# 6x6.net
KiCad netlist of a schematic drawn in EAGLE
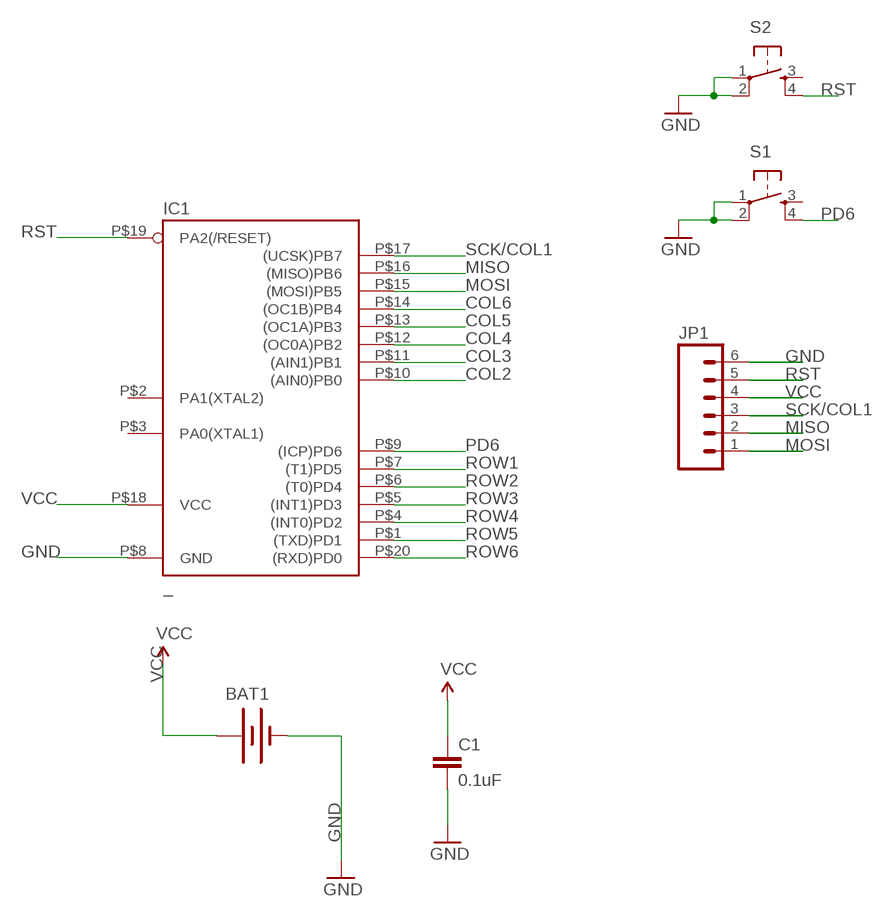
[diagram p0: schematic, sheet 1]
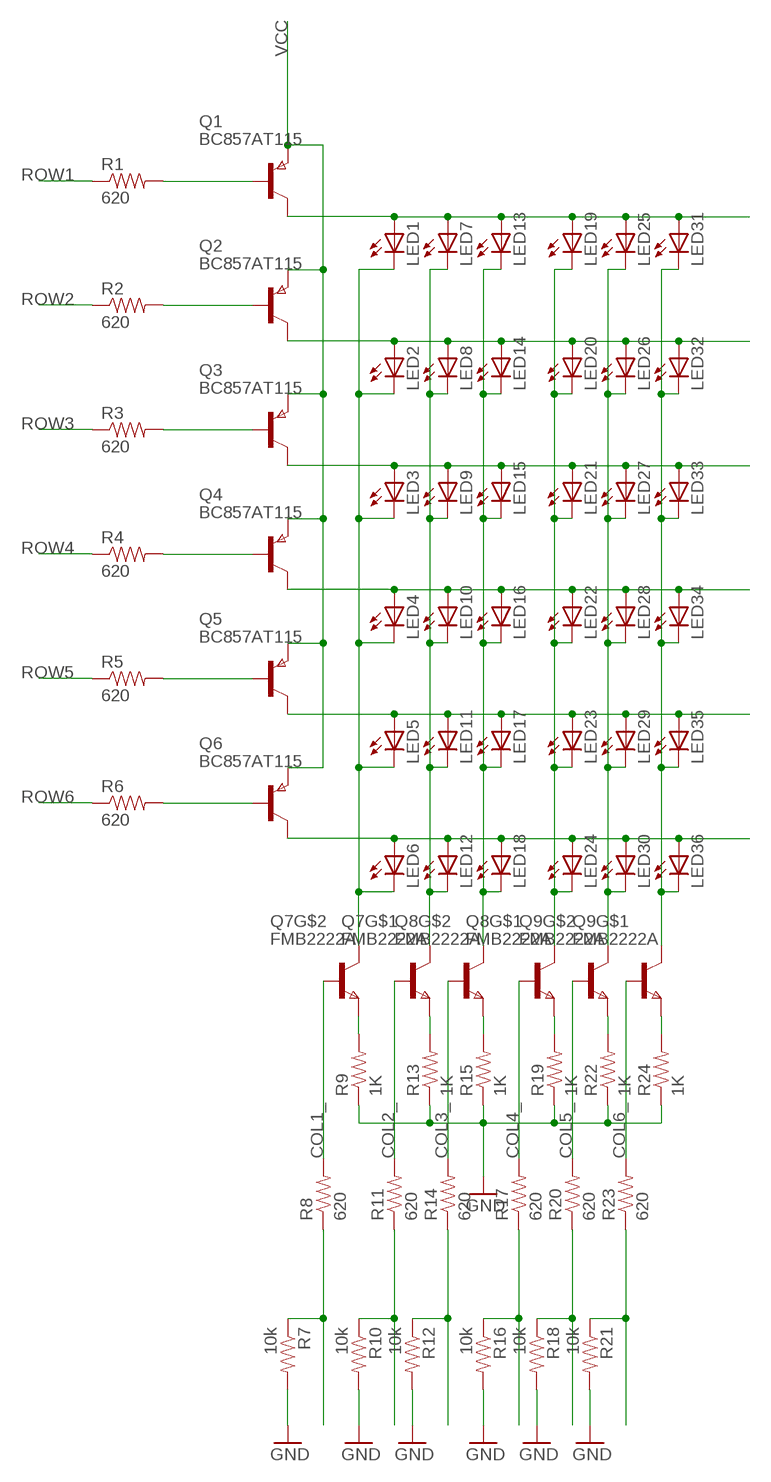
[diagram p1: schematic, sheet 2]

(export (version "E")
  (design (tool "Eeschema 10.0.6"))
  (components
    (comp (ref "BAT1")
      (value "BATTERY245MM")
      (footprint "eagle-import:BATTCON_245MM")
      (libsource (lib "eagle-import") (part "BATTERY245MM"))
    )
    (comp (ref "C1")
      (value "0.1uF")
      (footprint "eagle-import:0805")
      (libsource (lib "eagle-import") (part "CAP0805"))
    )
    (comp (ref "IC1")
      (value "_")
      (footprint "eagle-import:MLF20")
      (libsource (lib "eagle-import") (part "TINY2313-M"))
    )
    (comp (ref "JP1")
      (value "M061X06-SMD_EDGE_FEMALE")
      (footprint "eagle-import:1X06-SMD_EDGE")
      (libsource (lib "eagle-import") (part "M061X06-SMD_EDGE_FEMALE"))
    )
    (comp (ref "S1")
      (value "TAC_SWITCHSMD")
      (footprint "eagle-import:TACTILE_SWITCH_SMD")
      (libsource (lib "eagle-import") (part "TAC_SWITCHSMD"))
    )
    (comp (ref "S2")
      (value "TAC_SWITCHSMD")
      (footprint "eagle-import:TACTILE_SWITCH_SMD")
      (libsource (lib "eagle-import") (part "TAC_SWITCHSMD"))
    )
    (comp (ref "LED1")
      (value "LEDCHIPLED_1206")
      (footprint "eagle-import:CHIPLED_1206")
      (libsource (lib "eagle-import") (part "LEDCHIPLED_1206"))
    )
    (comp (ref "LED2")
      (value "LEDCHIPLED_1206")
      (footprint "eagle-import:CHIPLED_1206")
      (libsource (lib "eagle-import") (part "LEDCHIPLED_1206"))
    )
    (comp (ref "LED3")
      (value "LEDCHIPLED_1206")
      (footprint "eagle-import:CHIPLED_1206")
      (libsource (lib "eagle-import") (part "LEDCHIPLED_1206"))
    )
    (comp (ref "LED4")
      (value "LEDCHIPLED_1206")
      (footprint "eagle-import:CHIPLED_1206")
      (libsource (lib "eagle-import") (part "LEDCHIPLED_1206"))
    )
    (comp (ref "LED5")
      (value "LEDCHIPLED_1206")
      (footprint "eagle-import:CHIPLED_1206")
      (libsource (lib "eagle-import") (part "LEDCHIPLED_1206"))
    )
    (comp (ref "LED6")
      (value "LEDCHIPLED_1206")
      (footprint "eagle-import:CHIPLED_1206")
      (libsource (lib "eagle-import") (part "LEDCHIPLED_1206"))
    )
    (comp (ref "LED7")
      (value "LEDCHIPLED_1206")
      (footprint "eagle-import:CHIPLED_1206")
      (libsource (lib "eagle-import") (part "LEDCHIPLED_1206"))
    )
    (comp (ref "LED8")
      (value "LEDCHIPLED_1206")
      (footprint "eagle-import:CHIPLED_1206")
      (libsource (lib "eagle-import") (part "LEDCHIPLED_1206"))
    )
    (comp (ref "LED9")
      (value "LEDCHIPLED_1206")
      (footprint "eagle-import:CHIPLED_1206")
      (libsource (lib "eagle-import") (part "LEDCHIPLED_1206"))
    )
    (comp (ref "LED10")
      (value "LEDCHIPLED_1206")
      (footprint "eagle-import:CHIPLED_1206")
      (libsource (lib "eagle-import") (part "LEDCHIPLED_1206"))
    )
    (comp (ref "LED11")
      (value "LEDCHIPLED_1206")
      (footprint "eagle-import:CHIPLED_1206")
      (libsource (lib "eagle-import") (part "LEDCHIPLED_1206"))
    )
    (comp (ref "LED12")
      (value "LEDCHIPLED_1206")
      (footprint "eagle-import:CHIPLED_1206")
      (libsource (lib "eagle-import") (part "LEDCHIPLED_1206"))
    )
    (comp (ref "LED13")
      (value "LEDCHIPLED_1206")
      (footprint "eagle-import:CHIPLED_1206")
      (libsource (lib "eagle-import") (part "LEDCHIPLED_1206"))
    )
    (comp (ref "LED14")
      (value "LEDCHIPLED_1206")
      (footprint "eagle-import:CHIPLED_1206")
      (libsource (lib "eagle-import") (part "LEDCHIPLED_1206"))
    )
    (comp (ref "LED15")
      (value "LEDCHIPLED_1206")
      (footprint "eagle-import:CHIPLED_1206")
      (libsource (lib "eagle-import") (part "LEDCHIPLED_1206"))
    )
    (comp (ref "LED16")
      (value "LEDCHIPLED_1206")
      (footprint "eagle-import:CHIPLED_1206")
      (libsource (lib "eagle-import") (part "LEDCHIPLED_1206"))
    )
    (comp (ref "LED17")
      (value "LEDCHIPLED_1206")
      (footprint "eagle-import:CHIPLED_1206")
      (libsource (lib "eagle-import") (part "LEDCHIPLED_1206"))
    )
    (comp (ref "LED18")
      (value "LEDCHIPLED_1206")
      (footprint "eagle-import:CHIPLED_1206")
      (libsource (lib "eagle-import") (part "LEDCHIPLED_1206"))
    )
    (comp (ref "LED19")
      (value "LEDCHIPLED_1206")
      (footprint "eagle-import:CHIPLED_1206")
      (libsource (lib "eagle-import") (part "LEDCHIPLED_1206"))
    )
    (comp (ref "LED20")
      (value "LEDCHIPLED_1206")
      (footprint "eagle-import:CHIPLED_1206")
      (libsource (lib "eagle-import") (part "LEDCHIPLED_1206"))
    )
    (comp (ref "LED21")
      (value "LEDCHIPLED_1206")
      (footprint "eagle-import:CHIPLED_1206")
      (libsource (lib "eagle-import") (part "LEDCHIPLED_1206"))
    )
    (comp (ref "LED22")
      (value "LEDCHIPLED_1206")
      (footprint "eagle-import:CHIPLED_1206")
      (libsource (lib "eagle-import") (part "LEDCHIPLED_1206"))
    )
    (comp (ref "LED23")
      (value "LEDCHIPLED_1206")
      (footprint "eagle-import:CHIPLED_1206")
      (libsource (lib "eagle-import") (part "LEDCHIPLED_1206"))
    )
    (comp (ref "LED24")
      (value "LEDCHIPLED_1206")
      (footprint "eagle-import:CHIPLED_1206")
      (libsource (lib "eagle-import") (part "LEDCHIPLED_1206"))
    )
    (comp (ref "LED25")
      (value "LEDCHIPLED_1206")
      (footprint "eagle-import:CHIPLED_1206")
      (libsource (lib "eagle-import") (part "LEDCHIPLED_1206"))
    )
    (comp (ref "LED26")
      (value "LEDCHIPLED_1206")
      (footprint "eagle-import:CHIPLED_1206")
      (libsource (lib "eagle-import") (part "LEDCHIPLED_1206"))
    )
    (comp (ref "LED27")
      (value "LEDCHIPLED_1206")
      (footprint "eagle-import:CHIPLED_1206")
      (libsource (lib "eagle-import") (part "LEDCHIPLED_1206"))
    )
    (comp (ref "LED28")
      (value "LEDCHIPLED_1206")
      (footprint "eagle-import:CHIPLED_1206")
      (libsource (lib "eagle-import") (part "LEDCHIPLED_1206"))
    )
    (comp (ref "LED29")
      (value "LEDCHIPLED_1206")
      (footprint "eagle-import:CHIPLED_1206")
      (libsource (lib "eagle-import") (part "LEDCHIPLED_1206"))
    )
    (comp (ref "LED30")
      (value "LEDCHIPLED_1206")
      (footprint "eagle-import:CHIPLED_1206")
      (libsource (lib "eagle-import") (part "LEDCHIPLED_1206"))
    )
    (comp (ref "LED31")
      (value "LEDCHIPLED_1206")
      (footprint "eagle-import:CHIPLED_1206")
      (libsource (lib "eagle-import") (part "LEDCHIPLED_1206"))
    )
    (comp (ref "LED32")
      (value "LEDCHIPLED_1206")
      (footprint "eagle-import:CHIPLED_1206")
      (libsource (lib "eagle-import") (part "LEDCHIPLED_1206"))
    )
    (comp (ref "LED33")
      (value "LEDCHIPLED_1206")
      (footprint "eagle-import:CHIPLED_1206")
      (libsource (lib "eagle-import") (part "LEDCHIPLED_1206"))
    )
    (comp (ref "LED34")
      (value "LEDCHIPLED_1206")
      (footprint "eagle-import:CHIPLED_1206")
      (libsource (lib "eagle-import") (part "LEDCHIPLED_1206"))
    )
    (comp (ref "LED35")
      (value "LEDCHIPLED_1206")
      (footprint "eagle-import:CHIPLED_1206")
      (libsource (lib "eagle-import") (part "LEDCHIPLED_1206"))
    )
    (comp (ref "LED36")
      (value "LEDCHIPLED_1206")
      (footprint "eagle-import:CHIPLED_1206")
      (libsource (lib "eagle-import") (part "LEDCHIPLED_1206"))
    )
    (comp (ref "Q1")
      (value "BC857AT115")
      (footprint "eagle-import:SOT416")
      (libsource (lib "eagle-import") (part "PNPSOT323SOT416"))
    )
    (comp (ref "Q2")
      (value "BC857AT115")
      (footprint "eagle-import:SOT416")
      (libsource (lib "eagle-import") (part "PNPSOT323SOT416"))
    )
    (comp (ref "Q3")
      (value "BC857AT115")
      (footprint "eagle-import:SOT416")
      (libsource (lib "eagle-import") (part "PNPSOT323SOT416"))
    )
    (comp (ref "Q4")
      (value "BC857AT115")
      (footprint "eagle-import:SOT416")
      (libsource (lib "eagle-import") (part "PNPSOT323SOT416"))
    )
    (comp (ref "Q5")
      (value "BC857AT115")
      (footprint "eagle-import:SOT416")
      (libsource (lib "eagle-import") (part "PNPSOT323SOT416"))
    )
    (comp (ref "Q6")
      (value "BC857AT115")
      (footprint "eagle-import:SOT416")
      (libsource (lib "eagle-import") (part "PNPSOT323SOT416"))
    )
    (comp (ref "Q7")
      (value "FMB2222A")
      (footprint "eagle-import:SSOT6")
      (libsource (lib "eagle-import") (part "DUALNPN"))
    )
    (comp (ref "Q8")
      (value "FMB2222A")
      (footprint "eagle-import:SSOT6")
      (libsource (lib "eagle-import") (part "DUALNPN"))
    )
    (comp (ref "Q9")
      (value "FMB2222A")
      (footprint "eagle-import:SSOT6")
      (libsource (lib "eagle-import") (part "DUALNPN"))
    )
    (comp (ref "R1")
      (value "620")
      (footprint "eagle-import:SPARKFUN_0402-RES")
      (libsource (lib "eagle-import") (part "SPARKFUN_RESISTOR0402-RES"))
    )
    (comp (ref "R2")
      (value "620")
      (footprint "eagle-import:SPARKFUN_0603-RES")
      (libsource (lib "eagle-import") (part "SPARKFUN_RESISTOR0603-RES"))
    )
    (comp (ref "R3")
      (value "620")
      (footprint "eagle-import:SPARKFUN_0603-RES")
      (libsource (lib "eagle-import") (part "SPARKFUN_RESISTOR0603-RES"))
    )
    (comp (ref "R4")
      (value "620")
      (footprint "eagle-import:SPARKFUN_0603-RES")
      (libsource (lib "eagle-import") (part "SPARKFUN_RESISTOR0603-RES"))
    )
    (comp (ref "R5")
      (value "620")
      (footprint "eagle-import:SPARKFUN_0603-RES")
      (libsource (lib "eagle-import") (part "SPARKFUN_RESISTOR0603-RES"))
    )
    (comp (ref "R6")
      (value "620")
      (footprint "eagle-import:SPARKFUN_0603-RES")
      (libsource (lib "eagle-import") (part "SPARKFUN_RESISTOR0603-RES"))
    )
    (comp (ref "R7")
      (value "10k")
      (footprint "eagle-import:SPARKFUN_0603-RES")
      (libsource (lib "eagle-import") (part "SPARKFUN_RESISTOR0603-RES"))
    )
    (comp (ref "R8")
      (value "620")
      (footprint "eagle-import:SPARKFUN_0603-RES")
      (libsource (lib "eagle-import") (part "SPARKFUN_RESISTOR0603-RES"))
    )
    (comp (ref "R9")
      (value "1K")
      (footprint "eagle-import:SPARKFUN_0603-RES")
      (libsource (lib "eagle-import") (part "SPARKFUN_RESISTOR0603-RES"))
    )
    (comp (ref "R10")
      (value "10k")
      (footprint "eagle-import:SPARKFUN_0603-RES")
      (libsource (lib "eagle-import") (part "SPARKFUN_RESISTOR0603-RES"))
    )
    (comp (ref "R11")
      (value "620")
      (footprint "eagle-import:SPARKFUN_0603-RES")
      (libsource (lib "eagle-import") (part "SPARKFUN_RESISTOR0603-RES"))
    )
    (comp (ref "R12")
      (value "10k")
      (footprint "eagle-import:SPARKFUN_0603-RES")
      (libsource (lib "eagle-import") (part "SPARKFUN_RESISTOR0603-RES"))
    )
    (comp (ref "R13")
      (value "1K")
      (footprint "eagle-import:SPARKFUN_0603-RES")
      (libsource (lib "eagle-import") (part "SPARKFUN_RESISTOR0603-RES"))
    )
    (comp (ref "R14")
      (value "620")
      (footprint "eagle-import:SPARKFUN_0603-RES")
      (libsource (lib "eagle-import") (part "SPARKFUN_RESISTOR0603-RES"))
    )
    (comp (ref "R15")
      (value "1K")
      (footprint "eagle-import:SPARKFUN_0603-RES")
      (libsource (lib "eagle-import") (part "SPARKFUN_RESISTOR0603-RES"))
    )
    (comp (ref "R16")
      (value "10k")
      (footprint "eagle-import:SPARKFUN_0603-RES")
      (libsource (lib "eagle-import") (part "SPARKFUN_RESISTOR0603-RES"))
    )
    (comp (ref "R17")
      (value "620")
      (footprint "eagle-import:SPARKFUN_0603-RES")
      (libsource (lib "eagle-import") (part "SPARKFUN_RESISTOR0603-RES"))
    )
    (comp (ref "R18")
      (value "10k")
      (footprint "eagle-import:SPARKFUN_0603-RES")
      (libsource (lib "eagle-import") (part "SPARKFUN_RESISTOR0603-RES"))
    )
    (comp (ref "R19")
      (value "1K")
      (footprint "eagle-import:SPARKFUN_0603-RES")
      (libsource (lib "eagle-import") (part "SPARKFUN_RESISTOR0603-RES"))
    )
    (comp (ref "R20")
      (value "620")
      (footprint "eagle-import:SPARKFUN_0603-RES")
      (libsource (lib "eagle-import") (part "SPARKFUN_RESISTOR0603-RES"))
    )
    (comp (ref "R21")
      (value "10k")
      (footprint "eagle-import:SPARKFUN_0603-RES")
      (libsource (lib "eagle-import") (part "SPARKFUN_RESISTOR0603-RES"))
    )
    (comp (ref "R22")
      (value "1K")
      (footprint "eagle-import:SPARKFUN_0603-RES")
      (libsource (lib "eagle-import") (part "SPARKFUN_RESISTOR0603-RES"))
    )
    (comp (ref "R23")
      (value "620")
      (footprint "eagle-import:SPARKFUN_0603-RES")
      (libsource (lib "eagle-import") (part "SPARKFUN_RESISTOR0603-RES"))
    )
    (comp (ref "R24")
      (value "1K")
      (footprint "eagle-import:SPARKFUN_0603-RES")
      (libsource (lib "eagle-import") (part "SPARKFUN_RESISTOR0603-RES"))
    )
  )
  (nets
    (net (code "1") (name "COL1_") (class "Default")
      (node (ref "Q7") (pin "3") (pinfunction "B_3") (pintype "passive"))
      (node (ref "R8") (pin "2") (pinfunction "2_2") (pintype "passive"))
    )
    (net (code "2") (name "COL2") (class "Default")
      (node (ref "IC1") (pin "P$10") (pinfunction "(AIN0)PB0_P$10") (pintype "bidirectional"))
      (node (ref "R10") (pin "1") (pinfunction "1_1") (pintype "passive"))
      (node (ref "R11") (pin "1") (pinfunction "1_1") (pintype "passive"))
    )
    (net (code "3") (name "COL2_") (class "Default")
      (node (ref "Q7") (pin "1") (pinfunction "B_1") (pintype "passive"))
      (node (ref "R11") (pin "2") (pinfunction "2_2") (pintype "passive"))
    )
    (net (code "4") (name "COL3") (class "Default")
      (node (ref "IC1") (pin "P$11") (pinfunction "(AIN1)PB1_P$11") (pintype "bidirectional"))
      (node (ref "R12") (pin "1") (pinfunction "1_1") (pintype "passive"))
      (node (ref "R14") (pin "1") (pinfunction "1_1") (pintype "passive"))
    )
    (net (code "5") (name "COL3_") (class "Default")
      (node (ref "Q8") (pin "3") (pinfunction "B_3") (pintype "passive"))
      (node (ref "R14") (pin "2") (pinfunction "2_2") (pintype "passive"))
    )
    (net (code "6") (name "COL4") (class "Default")
      (node (ref "IC1") (pin "P$12") (pinfunction "(OC0A)PB2_P$12") (pintype "bidirectional"))
      (node (ref "R16") (pin "1") (pinfunction "1_1") (pintype "passive"))
      (node (ref "R17") (pin "1") (pinfunction "1_1") (pintype "passive"))
    )
    (net (code "7") (name "COL4_") (class "Default")
      (node (ref "Q8") (pin "1") (pinfunction "B_1") (pintype "passive"))
      (node (ref "R17") (pin "2") (pinfunction "2_2") (pintype "passive"))
    )
    (net (code "8") (name "COL5") (class "Default")
      (node (ref "IC1") (pin "P$13") (pinfunction "(OC1A)PB3_P$13") (pintype "bidirectional"))
      (node (ref "R18") (pin "1") (pinfunction "1_1") (pintype "passive"))
      (node (ref "R20") (pin "1") (pinfunction "1_1") (pintype "passive"))
    )
    (net (code "9") (name "COL5_") (class "Default")
      (node (ref "Q9") (pin "3") (pinfunction "B_3") (pintype "passive"))
      (node (ref "R20") (pin "2") (pinfunction "2_2") (pintype "passive"))
    )
    (net (code "10") (name "COL6") (class "Default")
      (node (ref "IC1") (pin "P$14") (pinfunction "(OC1B)PB4_P$14") (pintype "bidirectional"))
      (node (ref "R21") (pin "1") (pinfunction "1_1") (pintype "passive"))
      (node (ref "R23") (pin "1") (pinfunction "1_1") (pintype "passive"))
    )
    (net (code "11") (name "COL6_") (class "Default")
      (node (ref "Q9") (pin "1") (pinfunction "B_1") (pintype "passive"))
      (node (ref "R23") (pin "2") (pinfunction "2_2") (pintype "passive"))
    )
    (net (code "12") (name "GND") (class "Default")
      (node (ref "BAT1") (pin "2") (pinfunction "-_2") (pintype "power_in"))
      (node (ref "C1") (pin "2") (pinfunction "2_2") (pintype "passive"))
      (node (ref "IC1") (pin "P$8") (pinfunction "GND_P$8") (pintype "power_in"))
      (node (ref "JP1") (pin "6") (pinfunction "6_6") (pintype "passive"))
      (node (ref "R10") (pin "2") (pinfunction "2_2") (pintype "passive"))
      (node (ref "R12") (pin "2") (pinfunction "2_2") (pintype "passive"))
      (node (ref "R13") (pin "1") (pinfunction "1_1") (pintype "passive"))
      (node (ref "R15") (pin "1") (pinfunction "1_1") (pintype "passive"))
      (node (ref "R16") (pin "2") (pinfunction "2_2") (pintype "passive"))
      (node (ref "R18") (pin "2") (pinfunction "2_2") (pintype "passive"))
      (node (ref "R19") (pin "1") (pinfunction "1_1") (pintype "passive"))
      (node (ref "R21") (pin "2") (pinfunction "2_2") (pintype "passive"))
      (node (ref "R22") (pin "1") (pinfunction "1_1") (pintype "passive"))
      (node (ref "R24") (pin "1") (pinfunction "1_1") (pintype "passive"))
      (node (ref "R7") (pin "2") (pinfunction "2_2") (pintype "passive"))
      (node (ref "R9") (pin "1") (pinfunction "1_1") (pintype "passive"))
      (node (ref "S1") (pin "1") (pinfunction "1_1") (pintype "passive"))
      (node (ref "S1") (pin "2") (pinfunction "2_2") (pintype "passive"))
      (node (ref "S2") (pin "1") (pinfunction "1_1") (pintype "passive"))
      (node (ref "S2") (pin "2") (pinfunction "2_2") (pintype "passive"))
    )
    (net (code "13") (name "MISO") (class "Default")
      (node (ref "IC1") (pin "P$16") (pinfunction "(MISO)PB6_P$16") (pintype "bidirectional"))
      (node (ref "JP1") (pin "2") (pinfunction "2_2") (pintype "passive"))
    )
    (net (code "14") (name "MOSI") (class "Default")
      (node (ref "IC1") (pin "P$15") (pinfunction "(MOSI)PB5_P$15") (pintype "bidirectional"))
      (node (ref "JP1") (pin "1") (pinfunction "1_1") (pintype "passive"))
    )
    (net (code "15") (name "Net-(Q1-B)") (class "Default")
      (node (ref "Q1") (pin "2") (pinfunction "B_2") (pintype "passive"))
      (node (ref "R1") (pin "2") (pinfunction "2_2") (pintype "passive"))
    )
    (net (code "16") (name "Net-(Q1-C)") (class "Default")
      (node (ref "LED1") (pin "A") (pinfunction "A_A") (pintype "passive"))
      (node (ref "LED13") (pin "A") (pinfunction "A_A") (pintype "passive"))
      (node (ref "LED19") (pin "A") (pinfunction "A_A") (pintype "passive"))
      (node (ref "LED25") (pin "A") (pinfunction "A_A") (pintype "passive"))
      (node (ref "LED31") (pin "A") (pinfunction "A_A") (pintype "passive"))
      (node (ref "LED7") (pin "A") (pinfunction "A_A") (pintype "passive"))
      (node (ref "Q1") (pin "1") (pinfunction "C_1") (pintype "passive"))
    )
    (net (code "17") (name "Net-(Q2-B)") (class "Default")
      (node (ref "Q2") (pin "2") (pinfunction "B_2") (pintype "passive"))
      (node (ref "R2") (pin "2") (pinfunction "2_2") (pintype "passive"))
    )
    (net (code "18") (name "Net-(Q2-C)") (class "Default")
      (node (ref "LED14") (pin "A") (pinfunction "A_A") (pintype "passive"))
      (node (ref "LED2") (pin "A") (pinfunction "A_A") (pintype "passive"))
      (node (ref "LED20") (pin "A") (pinfunction "A_A") (pintype "passive"))
      (node (ref "LED26") (pin "A") (pinfunction "A_A") (pintype "passive"))
      (node (ref "LED32") (pin "A") (pinfunction "A_A") (pintype "passive"))
      (node (ref "LED8") (pin "A") (pinfunction "A_A") (pintype "passive"))
      (node (ref "Q2") (pin "1") (pinfunction "C_1") (pintype "passive"))
    )
    (net (code "19") (name "Net-(Q3-B)") (class "Default")
      (node (ref "Q3") (pin "2") (pinfunction "B_2") (pintype "passive"))
      (node (ref "R3") (pin "2") (pinfunction "2_2") (pintype "passive"))
    )
    (net (code "20") (name "Net-(Q3-C)") (class "Default")
      (node (ref "LED15") (pin "A") (pinfunction "A_A") (pintype "passive"))
      (node (ref "LED21") (pin "A") (pinfunction "A_A") (pintype "passive"))
      (node (ref "LED27") (pin "A") (pinfunction "A_A") (pintype "passive"))
      (node (ref "LED3") (pin "A") (pinfunction "A_A") (pintype "passive"))
      (node (ref "LED33") (pin "A") (pinfunction "A_A") (pintype "passive"))
      (node (ref "LED9") (pin "A") (pinfunction "A_A") (pintype "passive"))
      (node (ref "Q3") (pin "1") (pinfunction "C_1") (pintype "passive"))
    )
    (net (code "21") (name "Net-(Q4-B)") (class "Default")
      (node (ref "Q4") (pin "2") (pinfunction "B_2") (pintype "passive"))
      (node (ref "R4") (pin "2") (pinfunction "2_2") (pintype "passive"))
    )
    (net (code "22") (name "Net-(Q4-C)") (class "Default")
      (node (ref "LED10") (pin "A") (pinfunction "A_A") (pintype "passive"))
      (node (ref "LED16") (pin "A") (pinfunction "A_A") (pintype "passive"))
      (node (ref "LED22") (pin "A") (pinfunction "A_A") (pintype "passive"))
      (node (ref "LED28") (pin "A") (pinfunction "A_A") (pintype "passive"))
      (node (ref "LED34") (pin "A") (pinfunction "A_A") (pintype "passive"))
      (node (ref "LED4") (pin "A") (pinfunction "A_A") (pintype "passive"))
      (node (ref "Q4") (pin "1") (pinfunction "C_1") (pintype "passive"))
    )
    (net (code "23") (name "Net-(Q5-B)") (class "Default")
      (node (ref "Q5") (pin "2") (pinfunction "B_2") (pintype "passive"))
      (node (ref "R5") (pin "2") (pinfunction "2_2") (pintype "passive"))
    )
    (net (code "24") (name "Net-(Q5-C)") (class "Default")
      (node (ref "LED11") (pin "A") (pinfunction "A_A") (pintype "passive"))
      (node (ref "LED17") (pin "A") (pinfunction "A_A") (pintype "passive"))
      (node (ref "LED23") (pin "A") (pinfunction "A_A") (pintype "passive"))
      (node (ref "LED29") (pin "A") (pinfunction "A_A") (pintype "passive"))
      (node (ref "LED35") (pin "A") (pinfunction "A_A") (pintype "passive"))
      (node (ref "LED5") (pin "A") (pinfunction "A_A") (pintype "passive"))
      (node (ref "Q5") (pin "1") (pinfunction "C_1") (pintype "passive"))
    )
    (net (code "25") (name "Net-(Q6-B)") (class "Default")
      (node (ref "Q6") (pin "2") (pinfunction "B_2") (pintype "passive"))
      (node (ref "R6") (pin "2") (pinfunction "2_2") (pintype "passive"))
    )
    (net (code "26") (name "Net-(Q6-C)") (class "Default")
      (node (ref "LED12") (pin "A") (pinfunction "A_A") (pintype "passive"))
      (node (ref "LED18") (pin "A") (pinfunction "A_A") (pintype "passive"))
      (node (ref "LED24") (pin "A") (pinfunction "A_A") (pintype "passive"))
      (node (ref "LED30") (pin "A") (pinfunction "A_A") (pintype "passive"))
      (node (ref "LED36") (pin "A") (pinfunction "A_A") (pintype "passive"))
      (node (ref "LED6") (pin "A") (pinfunction "A_A") (pintype "passive"))
      (node (ref "Q6") (pin "1") (pinfunction "C_1") (pintype "passive"))
    )
    (net (code "27") (name "Net-(Q7A-C)") (class "Default")
      (node (ref "LED10") (pin "C") (pinfunction "C_C") (pintype "passive"))
      (node (ref "LED11") (pin "C") (pinfunction "C_C") (pintype "passive"))
      (node (ref "LED12") (pin "C") (pinfunction "C_C") (pintype "passive"))
      (node (ref "LED7") (pin "C") (pinfunction "C_C") (pintype "passive"))
      (node (ref "LED8") (pin "C") (pinfunction "C_C") (pintype "passive"))
      (node (ref "LED9") (pin "C") (pinfunction "C_C") (pintype "passive"))
      (node (ref "Q7") (pin "6") (pinfunction "C_6") (pintype "passive"))
    )
    (net (code "28") (name "Net-(Q7A-E)") (class "Default")
      (node (ref "Q7") (pin "5") (pinfunction "E_5") (pintype "passive"))
      (node (ref "R13") (pin "2") (pinfunction "2_2") (pintype "passive"))
    )
    (net (code "29") (name "Net-(Q7B-C)") (class "Default")
      (node (ref "LED1") (pin "C") (pinfunction "C_C") (pintype "passive"))
      (node (ref "LED2") (pin "C") (pinfunction "C_C") (pintype "passive"))
      (node (ref "LED3") (pin "C") (pinfunction "C_C") (pintype "passive"))
      (node (ref "LED4") (pin "C") (pinfunction "C_C") (pintype "passive"))
      (node (ref "LED5") (pin "C") (pinfunction "C_C") (pintype "passive"))
      (node (ref "LED6") (pin "C") (pinfunction "C_C") (pintype "passive"))
      (node (ref "Q7") (pin "4") (pinfunction "C_4") (pintype "passive"))
    )
    (net (code "30") (name "Net-(Q7B-E)") (class "Default")
      (node (ref "Q7") (pin "2") (pinfunction "E_2") (pintype "passive"))
      (node (ref "R9") (pin "2") (pinfunction "2_2") (pintype "passive"))
    )
    (net (code "31") (name "Net-(Q8A-C)") (class "Default")
      (node (ref "LED19") (pin "C") (pinfunction "C_C") (pintype "passive"))
      (node (ref "LED20") (pin "C") (pinfunction "C_C") (pintype "passive"))
      (node (ref "LED21") (pin "C") (pinfunction "C_C") (pintype "passive"))
      (node (ref "LED22") (pin "C") (pinfunction "C_C") (pintype "passive"))
      (node (ref "LED23") (pin "C") (pinfunction "C_C") (pintype "passive"))
      (node (ref "LED24") (pin "C") (pinfunction "C_C") (pintype "passive"))
      (node (ref "Q8") (pin "6") (pinfunction "C_6") (pintype "passive"))
    )
    (net (code "32") (name "Net-(Q8A-E)") (class "Default")
      (node (ref "Q8") (pin "5") (pinfunction "E_5") (pintype "passive"))
      (node (ref "R19") (pin "2") (pinfunction "2_2") (pintype "passive"))
    )
    (net (code "33") (name "Net-(Q8B-C)") (class "Default")
      (node (ref "LED13") (pin "C") (pinfunction "C_C") (pintype "passive"))
      (node (ref "LED14") (pin "C") (pinfunction "C_C") (pintype "passive"))
      (node (ref "LED15") (pin "C") (pinfunction "C_C") (pintype "passive"))
      (node (ref "LED16") (pin "C") (pinfunction "C_C") (pintype "passive"))
      (node (ref "LED17") (pin "C") (pinfunction "C_C") (pintype "passive"))
      (node (ref "LED18") (pin "C") (pinfunction "C_C") (pintype "passive"))
      (node (ref "Q8") (pin "4") (pinfunction "C_4") (pintype "passive"))
    )
    (net (code "34") (name "Net-(Q8B-E)") (class "Default")
      (node (ref "Q8") (pin "2") (pinfunction "E_2") (pintype "passive"))
      (node (ref "R15") (pin "2") (pinfunction "2_2") (pintype "passive"))
    )
    (net (code "35") (name "Net-(Q9A-C)") (class "Default")
      (node (ref "LED31") (pin "C") (pinfunction "C_C") (pintype "passive"))
      (node (ref "LED32") (pin "C") (pinfunction "C_C") (pintype "passive"))
      (node (ref "LED33") (pin "C") (pinfunction "C_C") (pintype "passive"))
      (node (ref "LED34") (pin "C") (pinfunction "C_C") (pintype "passive"))
      (node (ref "LED35") (pin "C") (pinfunction "C_C") (pintype "passive"))
      (node (ref "LED36") (pin "C") (pinfunction "C_C") (pintype "passive"))
      (node (ref "Q9") (pin "6") (pinfunction "C_6") (pintype "passive"))
    )
    (net (code "36") (name "Net-(Q9A-E)") (class "Default")
      (node (ref "Q9") (pin "5") (pinfunction "E_5") (pintype "passive"))
      (node (ref "R24") (pin "2") (pinfunction "2_2") (pintype "passive"))
    )
    (net (code "37") (name "Net-(Q9B-C)") (class "Default")
      (node (ref "LED25") (pin "C") (pinfunction "C_C") (pintype "passive"))
      (node (ref "LED26") (pin "C") (pinfunction "C_C") (pintype "passive"))
      (node (ref "LED27") (pin "C") (pinfunction "C_C") (pintype "passive"))
      (node (ref "LED28") (pin "C") (pinfunction "C_C") (pintype "passive"))
      (node (ref "LED29") (pin "C") (pinfunction "C_C") (pintype "passive"))
      (node (ref "LED30") (pin "C") (pinfunction "C_C") (pintype "passive"))
      (node (ref "Q9") (pin "4") (pinfunction "C_4") (pintype "passive"))
    )
    (net (code "38") (name "Net-(Q9B-E)") (class "Default")
      (node (ref "Q9") (pin "2") (pinfunction "E_2") (pintype "passive"))
      (node (ref "R22") (pin "2") (pinfunction "2_2") (pintype "passive"))
    )
    (net (code "39") (name "PD6") (class "Default")
      (node (ref "IC1") (pin "P$9") (pinfunction "(ICP)PD6_P$9") (pintype "bidirectional"))
      (node (ref "S1") (pin "4") (pinfunction "4_4") (pintype "passive"))
    )
    (net (code "40") (name "ROW1") (class "Default")
      (node (ref "IC1") (pin "P$7") (pinfunction "(T1)PD5_P$7") (pintype "bidirectional"))
      (node (ref "R1") (pin "1") (pinfunction "1_1") (pintype "passive"))
    )
    (net (code "41") (name "ROW2") (class "Default")
      (node (ref "IC1") (pin "P$6") (pinfunction "(T0)PD4_P$6") (pintype "bidirectional"))
      (node (ref "R2") (pin "1") (pinfunction "1_1") (pintype "passive"))
    )
    (net (code "42") (name "ROW3") (class "Default")
      (node (ref "IC1") (pin "P$5") (pinfunction "(INT1)PD3_P$5") (pintype "bidirectional"))
      (node (ref "R3") (pin "1") (pinfunction "1_1") (pintype "passive"))
    )
    (net (code "43") (name "ROW4") (class "Default")
      (node (ref "IC1") (pin "P$4") (pinfunction "(INT0)PD2_P$4") (pintype "bidirectional"))
      (node (ref "R4") (pin "1") (pinfunction "1_1") (pintype "passive"))
    )
    (net (code "44") (name "ROW5") (class "Default")
      (node (ref "IC1") (pin "P$1") (pinfunction "(TXD)PD1_P$1") (pintype "bidirectional"))
      (node (ref "R5") (pin "1") (pinfunction "1_1") (pintype "passive"))
    )
    (net (code "45") (name "ROW6") (class "Default")
      (node (ref "IC1") (pin "P$20") (pinfunction "(RXD)PD0_P$20") (pintype "bidirectional"))
      (node (ref "R6") (pin "1") (pinfunction "1_1") (pintype "passive"))
    )
    (net (code "46") (name "RST") (class "Default")
      (node (ref "IC1") (pin "P$19") (pinfunction "PA2(/RESET)_P$19") (pintype "input"))
      (node (ref "JP1") (pin "5") (pinfunction "5_5") (pintype "passive"))
      (node (ref "S2") (pin "4") (pinfunction "4_4") (pintype "passive"))
    )
    (net (code "47") (name "SCK{slash}COL1") (class "Default")
      (node (ref "IC1") (pin "P$17") (pinfunction "(UCSK)PB7_P$17") (pintype "bidirectional"))
      (node (ref "JP1") (pin "3") (pinfunction "3_3") (pintype "passive"))
      (node (ref "R7") (pin "1") (pinfunction "1_1") (pintype "passive"))
      (node (ref "R8") (pin "1") (pinfunction "1_1") (pintype "passive"))
    )
    (net (code "48") (name "VCC") (class "Default")
      (node (ref "BAT1") (pin "3") (pinfunction "+_3") (pintype "power_in"))
      (node (ref "C1") (pin "1") (pinfunction "1_1") (pintype "passive"))
      (node (ref "IC1") (pin "P$18") (pinfunction "VCC_P$18") (pintype "power_in"))
      (node (ref "JP1") (pin "4") (pinfunction "4_4") (pintype "passive"))
      (node (ref "Q1") (pin "3") (pinfunction "E_3") (pintype "passive"))
      (node (ref "Q2") (pin "3") (pinfunction "E_3") (pintype "passive"))
      (node (ref "Q3") (pin "3") (pinfunction "E_3") (pintype "passive"))
      (node (ref "Q4") (pin "3") (pinfunction "E_3") (pintype "passive"))
      (node (ref "Q5") (pin "3") (pinfunction "E_3") (pintype "passive"))
      (node (ref "Q6") (pin "3") (pinfunction "E_3") (pintype "passive"))
    )
    (net (code "49") (name "unconnected-(IC1-PA0(XTAL1)-PadP$3)") (class "Default")
      (node (ref "IC1") (pin "P$3") (pinfunction "PA0(XTAL1)_P$3") (pintype "bidirectional"))
    )
    (net (code "50") (name "unconnected-(IC1-PA1(XTAL2)-PadP$2)") (class "Default")
      (node (ref "IC1") (pin "P$2") (pinfunction "PA1(XTAL2)_P$2") (pintype "bidirectional"))
    )
    (net (code "51") (name "unconnected-(S1-Pad3)") (class "Default")
      (node (ref "S1") (pin "3") (pinfunction "3_3") (pintype "passive"))
    )
    (net (code "52") (name "unconnected-(S2-Pad3)") (class "Default")
      (node (ref "S2") (pin "3") (pinfunction "3_3") (pintype "passive"))
    )
  )
)
